# iPhone11-2WAI.net
KiCad netlist of a schematic drawn in Altium Designer
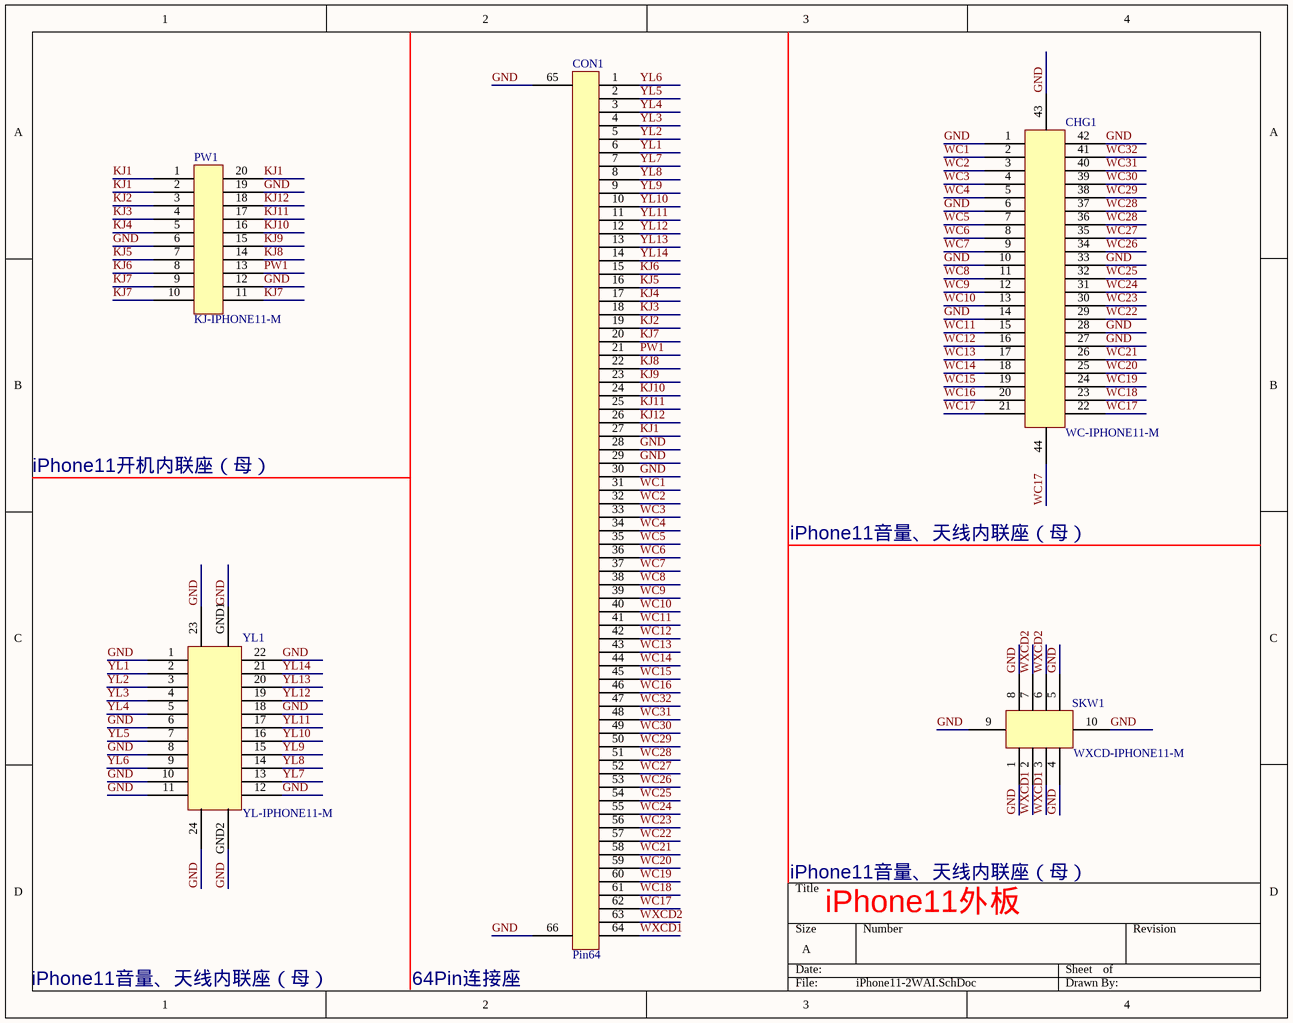
[diagram p0: iPhone11-2WAI.SchDoc]

(export (version "E")
  (design (tool "Eeschema 10.0.6"))
  (components
    (comp (ref "CHG1")
      (value "WC-IPHONE11-M")
      (footprint "IPHONE11-WC-M")
      (libsource (lib "iPhone") (part "WC-IPHONE11-M"))
    )
    (comp (ref "CON1") (value "Pin64") (footprint "Pin64") (libsource (lib "iPhone") (part "Pin64")))
    (comp (ref "PW1")
      (value "KJ-IPHONE11-M")
      (footprint "IPHONE11-KJ-M")
      (libsource (lib "iPhone") (part "KJ-IPHONE11-M"))
    )
    (comp (ref "SKW1")
      (value "WXCD-IPHONE11-M")
      (footprint "IPHONE11-WXCD-M")
      (libsource (lib "iPhone") (part "WXCD-IPHONE11-M"))
    )
    (comp (ref "YL1")
      (value "YL-IPHONE11-M")
      (footprint "IPHONE11-YL-M")
      (libsource (lib "iPhone") (part "YL-IPHONE11-M"))
    )
  )
  (nets
    (net (code "1") (name "/GND") (class "Default")
      (node (ref "CHG1") (pin "1") (pintype "passive"))
      (node (ref "CHG1") (pin "10") (pintype "passive"))
      (node (ref "CHG1") (pin "14") (pintype "passive"))
      (node (ref "CHG1") (pin "27") (pintype "passive"))
      (node (ref "CHG1") (pin "28") (pintype "passive"))
      (node (ref "CHG1") (pin "33") (pintype "passive"))
      (node (ref "CHG1") (pin "42") (pintype "passive"))
      (node (ref "CHG1") (pin "43") (pintype "passive"))
      (node (ref "CHG1") (pin "6") (pintype "passive"))
      (node (ref "CON1") (pin "28") (pintype "passive"))
      (node (ref "CON1") (pin "29") (pintype "passive"))
      (node (ref "CON1") (pin "30") (pintype "passive"))
      (node (ref "CON1") (pin "65") (pintype "passive"))
      (node (ref "CON1") (pin "66") (pintype "passive"))
      (node (ref "PW1") (pin "12") (pintype "passive"))
      (node (ref "PW1") (pin "19") (pintype "passive"))
      (node (ref "PW1") (pin "6") (pintype "passive"))
      (node (ref "SKW1") (pin "1") (pintype "passive"))
      (node (ref "SKW1") (pin "10") (pintype "passive"))
      (node (ref "SKW1") (pin "4") (pintype "passive"))
      (node (ref "SKW1") (pin "5") (pintype "passive"))
      (node (ref "SKW1") (pin "8") (pintype "passive"))
      (node (ref "SKW1") (pin "9") (pintype "passive"))
      (node (ref "YL1") (pin "1") (pintype "passive"))
      (node (ref "YL1") (pin "10") (pintype "passive"))
      (node (ref "YL1") (pin "11") (pintype "passive"))
      (node (ref "YL1") (pin "12") (pintype "passive"))
      (node (ref "YL1") (pin "18") (pintype "passive"))
      (node (ref "YL1") (pin "22") (pintype "passive"))
      (node (ref "YL1") (pin "23") (pintype "passive"))
      (node (ref "YL1") (pin "24") (pintype "passive"))
      (node (ref "YL1") (pin "6") (pintype "passive"))
      (node (ref "YL1") (pin "8") (pintype "passive"))
      (node (ref "YL1") (pin "GND1") (pintype "passive"))
      (node (ref "YL1") (pin "GND2") (pintype "passive"))
    )
    (net (code "2") (name "/KJ1") (class "Default")
      (node (ref "CON1") (pin "27") (pintype "passive"))
      (node (ref "PW1") (pin "1") (pintype "passive"))
      (node (ref "PW1") (pin "2") (pintype "passive"))
      (node (ref "PW1") (pin "20") (pintype "passive"))
    )
    (net (code "3") (name "/KJ2") (class "Default")
      (node (ref "CON1") (pin "19") (pintype "passive"))
      (node (ref "PW1") (pin "3") (pintype "passive"))
    )
    (net (code "4") (name "/KJ3") (class "Default")
      (node (ref "CON1") (pin "18") (pintype "passive"))
      (node (ref "PW1") (pin "4") (pintype "passive"))
    )
    (net (code "5") (name "/KJ4") (class "Default")
      (node (ref "CON1") (pin "17") (pintype "passive"))
      (node (ref "PW1") (pin "5") (pintype "passive"))
    )
    (net (code "6") (name "/KJ5") (class "Default")
      (node (ref "CON1") (pin "16") (pintype "passive"))
      (node (ref "PW1") (pin "7") (pintype "passive"))
    )
    (net (code "7") (name "/KJ6") (class "Default")
      (node (ref "CON1") (pin "15") (pintype "passive"))
      (node (ref "PW1") (pin "8") (pintype "passive"))
    )
    (net (code "8") (name "/KJ7") (class "Default")
      (node (ref "CON1") (pin "20") (pintype "passive"))
      (node (ref "PW1") (pin "10") (pintype "passive"))
      (node (ref "PW1") (pin "11") (pintype "passive"))
      (node (ref "PW1") (pin "9") (pintype "passive"))
    )
    (net (code "9") (name "/KJ8") (class "Default")
      (node (ref "CON1") (pin "22") (pintype "passive"))
      (node (ref "PW1") (pin "14") (pintype "passive"))
    )
    (net (code "10") (name "/KJ9") (class "Default")
      (node (ref "CON1") (pin "23") (pintype "passive"))
      (node (ref "PW1") (pin "15") (pintype "passive"))
    )
    (net (code "11") (name "/KJ10") (class "Default")
      (node (ref "CON1") (pin "24") (pintype "passive"))
      (node (ref "PW1") (pin "16") (pintype "passive"))
    )
    (net (code "12") (name "/KJ11") (class "Default")
      (node (ref "CON1") (pin "25") (pintype "passive"))
      (node (ref "PW1") (pin "17") (pintype "passive"))
    )
    (net (code "13") (name "/KJ12") (class "Default")
      (node (ref "CON1") (pin "26") (pintype "passive"))
      (node (ref "PW1") (pin "18") (pintype "passive"))
    )
    (net (code "14") (name "/PW1") (class "Default")
      (node (ref "CON1") (pin "21") (pintype "passive"))
      (node (ref "PW1") (pin "13") (pintype "passive"))
    )
    (net (code "15") (name "/WC1") (class "Default")
      (node (ref "CHG1") (pin "2") (pintype "passive"))
      (node (ref "CON1") (pin "31") (pintype "passive"))
    )
    (net (code "16") (name "/WC2") (class "Default")
      (node (ref "CHG1") (pin "3") (pintype "passive"))
      (node (ref "CON1") (pin "32") (pintype "passive"))
    )
    (net (code "17") (name "/WC3") (class "Default")
      (node (ref "CHG1") (pin "4") (pintype "passive"))
      (node (ref "CON1") (pin "33") (pintype "passive"))
    )
    (net (code "18") (name "/WC4") (class "Default")
      (node (ref "CHG1") (pin "5") (pintype "passive"))
      (node (ref "CON1") (pin "34") (pintype "passive"))
    )
    (net (code "19") (name "/WC5") (class "Default")
      (node (ref "CHG1") (pin "7") (pintype "passive"))
      (node (ref "CON1") (pin "35") (pintype "passive"))
    )
    (net (code "20") (name "/WC6") (class "Default")
      (node (ref "CHG1") (pin "8") (pintype "passive"))
      (node (ref "CON1") (pin "36") (pintype "passive"))
    )
    (net (code "21") (name "/WC7") (class "Default")
      (node (ref "CHG1") (pin "9") (pintype "passive"))
      (node (ref "CON1") (pin "37") (pintype "passive"))
    )
    (net (code "22") (name "/WC8") (class "Default")
      (node (ref "CHG1") (pin "11") (pintype "passive"))
      (node (ref "CON1") (pin "38") (pintype "passive"))
    )
    (net (code "23") (name "/WC9") (class "Default")
      (node (ref "CHG1") (pin "12") (pintype "passive"))
      (node (ref "CON1") (pin "39") (pintype "passive"))
    )
    (net (code "24") (name "/WC10") (class "Default")
      (node (ref "CHG1") (pin "13") (pintype "passive"))
      (node (ref "CON1") (pin "40") (pintype "passive"))
    )
    (net (code "25") (name "/WC11") (class "Default")
      (node (ref "CHG1") (pin "15") (pintype "passive"))
      (node (ref "CON1") (pin "41") (pintype "passive"))
    )
    (net (code "26") (name "/WC12") (class "Default")
      (node (ref "CHG1") (pin "16") (pintype "passive"))
      (node (ref "CON1") (pin "42") (pintype "passive"))
    )
    (net (code "27") (name "/WC13") (class "Default")
      (node (ref "CHG1") (pin "17") (pintype "passive"))
      (node (ref "CON1") (pin "43") (pintype "passive"))
    )
    (net (code "28") (name "/WC14") (class "Default")
      (node (ref "CHG1") (pin "18") (pintype "passive"))
      (node (ref "CON1") (pin "44") (pintype "passive"))
    )
    (net (code "29") (name "/WC15") (class "Default")
      (node (ref "CHG1") (pin "19") (pintype "passive"))
      (node (ref "CON1") (pin "45") (pintype "passive"))
    )
    (net (code "30") (name "/WC16") (class "Default")
      (node (ref "CHG1") (pin "20") (pintype "passive"))
      (node (ref "CON1") (pin "46") (pintype "passive"))
    )
    (net (code "31") (name "/WC17") (class "Default")
      (node (ref "CHG1") (pin "21") (pintype "passive"))
      (node (ref "CHG1") (pin "22") (pintype "passive"))
      (node (ref "CHG1") (pin "44") (pintype "passive"))
      (node (ref "CON1") (pin "62") (pintype "passive"))
    )
    (net (code "32") (name "/WC18") (class "Default")
      (node (ref "CHG1") (pin "23") (pintype "passive"))
      (node (ref "CON1") (pin "61") (pintype "passive"))
    )
    (net (code "33") (name "/WC19") (class "Default")
      (node (ref "CHG1") (pin "24") (pintype "passive"))
      (node (ref "CON1") (pin "60") (pintype "passive"))
    )
    (net (code "34") (name "/WC20") (class "Default")
      (node (ref "CHG1") (pin "25") (pintype "passive"))
      (node (ref "CON1") (pin "59") (pintype "passive"))
    )
    (net (code "35") (name "/WC21") (class "Default")
      (node (ref "CHG1") (pin "26") (pintype "passive"))
      (node (ref "CON1") (pin "58") (pintype "passive"))
    )
    (net (code "36") (name "/WC22") (class "Default")
      (node (ref "CHG1") (pin "29") (pintype "passive"))
      (node (ref "CON1") (pin "57") (pintype "passive"))
    )
    (net (code "37") (name "/WC23") (class "Default")
      (node (ref "CHG1") (pin "30") (pintype "passive"))
      (node (ref "CON1") (pin "56") (pintype "passive"))
    )
    (net (code "38") (name "/WC24") (class "Default")
      (node (ref "CHG1") (pin "31") (pintype "passive"))
      (node (ref "CON1") (pin "55") (pintype "passive"))
    )
    (net (code "39") (name "/WC25") (class "Default")
      (node (ref "CHG1") (pin "32") (pintype "passive"))
      (node (ref "CON1") (pin "54") (pintype "passive"))
    )
    (net (code "40") (name "/WC26") (class "Default")
      (node (ref "CHG1") (pin "34") (pintype "passive"))
      (node (ref "CON1") (pin "53") (pintype "passive"))
    )
    (net (code "41") (name "/WC27") (class "Default")
      (node (ref "CHG1") (pin "35") (pintype "passive"))
      (node (ref "CON1") (pin "52") (pintype "passive"))
    )
    (net (code "42") (name "/WC28") (class "Default")
      (node (ref "CHG1") (pin "36") (pintype "passive"))
      (node (ref "CHG1") (pin "37") (pintype "passive"))
      (node (ref "CON1") (pin "51") (pintype "passive"))
    )
    (net (code "43") (name "/WC29") (class "Default")
      (node (ref "CHG1") (pin "38") (pintype "passive"))
      (node (ref "CON1") (pin "50") (pintype "passive"))
    )
    (net (code "44") (name "/WC30") (class "Default")
      (node (ref "CHG1") (pin "39") (pintype "passive"))
      (node (ref "CON1") (pin "49") (pintype "passive"))
    )
    (net (code "45") (name "/WC31") (class "Default")
      (node (ref "CHG1") (pin "40") (pintype "passive"))
      (node (ref "CON1") (pin "48") (pintype "passive"))
    )
    (net (code "46") (name "/WC32") (class "Default")
      (node (ref "CHG1") (pin "41") (pintype "passive"))
      (node (ref "CON1") (pin "47") (pintype "passive"))
    )
    (net (code "47") (name "/WXCD1") (class "Default")
      (node (ref "CON1") (pin "64") (pintype "passive"))
      (node (ref "SKW1") (pin "2") (pintype "passive"))
      (node (ref "SKW1") (pin "3") (pintype "passive"))
    )
    (net (code "48") (name "/WXCD2") (class "Default")
      (node (ref "CON1") (pin "63") (pintype "passive"))
      (node (ref "SKW1") (pin "6") (pintype "passive"))
      (node (ref "SKW1") (pin "7") (pintype "passive"))
    )
    (net (code "49") (name "/YL1") (class "Default")
      (node (ref "CON1") (pin "6") (pintype "passive"))
      (node (ref "YL1") (pin "2") (pintype "passive"))
    )
    (net (code "50") (name "/YL2") (class "Default")
      (node (ref "CON1") (pin "5") (pintype "passive"))
      (node (ref "YL1") (pin "3") (pintype "passive"))
    )
    (net (code "51") (name "/YL3") (class "Default")
      (node (ref "CON1") (pin "4") (pintype "passive"))
      (node (ref "YL1") (pin "4") (pintype "passive"))
    )
    (net (code "52") (name "/YL4") (class "Default")
      (node (ref "CON1") (pin "3") (pintype "passive"))
      (node (ref "YL1") (pin "5") (pintype "passive"))
    )
    (net (code "53") (name "/YL5") (class "Default")
      (node (ref "CON1") (pin "2") (pintype "passive"))
      (node (ref "YL1") (pin "7") (pintype "passive"))
    )
    (net (code "54") (name "/YL6") (class "Default")
      (node (ref "CON1") (pin "1") (pintype "passive"))
      (node (ref "YL1") (pin "9") (pintype "passive"))
    )
    (net (code "55") (name "/YL7") (class "Default")
      (node (ref "CON1") (pin "7") (pintype "passive"))
      (node (ref "YL1") (pin "13") (pintype "passive"))
    )
    (net (code "56") (name "/YL8") (class "Default")
      (node (ref "CON1") (pin "8") (pintype "passive"))
      (node (ref "YL1") (pin "14") (pintype "passive"))
    )
    (net (code "57") (name "/YL9") (class "Default")
      (node (ref "CON1") (pin "9") (pintype "passive"))
      (node (ref "YL1") (pin "15") (pintype "passive"))
    )
    (net (code "58") (name "/YL10") (class "Default")
      (node (ref "CON1") (pin "10") (pintype "passive"))
      (node (ref "YL1") (pin "16") (pintype "passive"))
    )
    (net (code "59") (name "/YL11") (class "Default")
      (node (ref "CON1") (pin "11") (pintype "passive"))
      (node (ref "YL1") (pin "17") (pintype "passive"))
    )
    (net (code "60") (name "/YL12") (class "Default")
      (node (ref "CON1") (pin "12") (pintype "passive"))
      (node (ref "YL1") (pin "19") (pintype "passive"))
    )
    (net (code "61") (name "/YL13") (class "Default")
      (node (ref "CON1") (pin "13") (pintype "passive"))
      (node (ref "YL1") (pin "20") (pintype "passive"))
    )
    (net (code "62") (name "/YL14") (class "Default")
      (node (ref "CON1") (pin "14") (pintype "passive"))
      (node (ref "YL1") (pin "21") (pintype "passive"))
    )
  )
)
